# Homework2.net
KiCad netlist of a schematic drawn in EAGLE
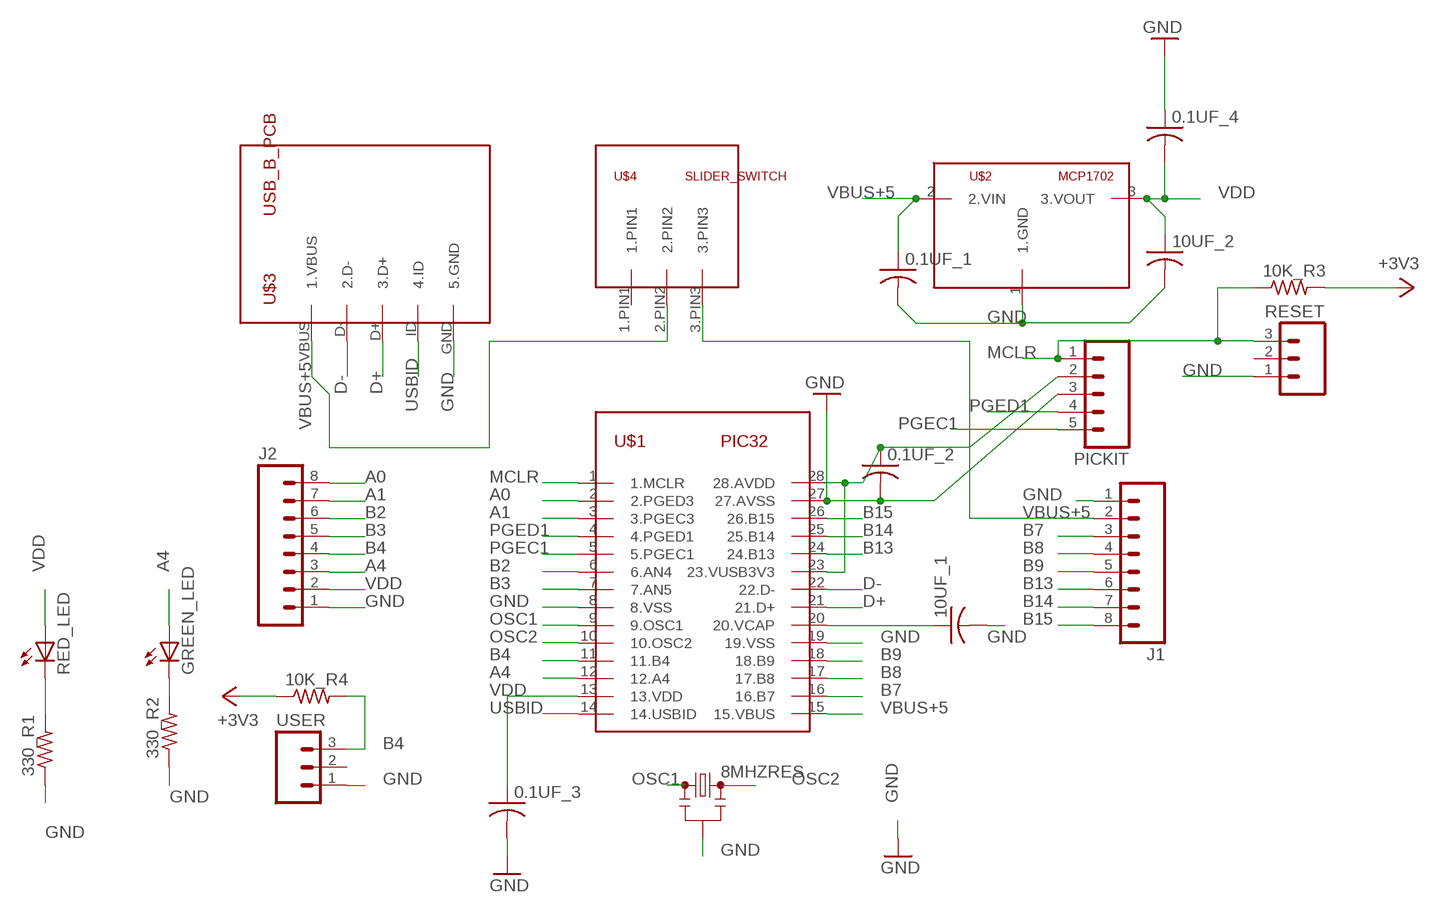
[diagram p0: schematic, sheet 1]

(export (version "E")
  (design (tool "Eeschema 10.0.6"))
  (components
    (comp (ref "0.1UF_1")
      (value "C-US025-024X044")
      (footprint "eagle-import:C025-024X044")
      (libsource (lib "eagle-import") (part "C-US025-024X044"))
    )
    (comp (ref "0.1UF_2")
      (value "C-US025-024X044")
      (footprint "eagle-import:C025-024X044")
      (libsource (lib "eagle-import") (part "C-US025-024X044"))
    )
    (comp (ref "0.1UF_3")
      (value "C-US025-024X044")
      (footprint "eagle-import:C025-024X044")
      (libsource (lib "eagle-import") (part "C-US025-024X044"))
    )
    (comp (ref "0.1UF_4")
      (value "C-US025-024X044")
      (footprint "eagle-import:C025-024X044")
      (libsource (lib "eagle-import") (part "C-US025-024X044"))
    )
    (comp (ref "8MHZRES")
      (value "RESONATORPTH")
      (footprint "eagle-import:RESONATOR-PTH")
      (libsource (lib "eagle-import") (part "RESONATORPTH"))
    )
    (comp (ref "10K_R3")
      (value "R-US_0204/5")
      (footprint "eagle-import:0204_5")
      (libsource (lib "eagle-import") (part "R-US_0204/5"))
    )
    (comp (ref "10K_R4")
      (value "R-US_0204/5")
      (footprint "eagle-import:0204_5")
      (libsource (lib "eagle-import") (part "R-US_0204/5"))
    )
    (comp (ref "10UF_1")
      (value "C-US050-024X044")
      (footprint "eagle-import:C050-024X044")
      (libsource (lib "eagle-import") (part "C-US050-024X044"))
    )
    (comp (ref "10UF_2")
      (value "C-US050-024X044")
      (footprint "eagle-import:C050-024X044")
      (libsource (lib "eagle-import") (part "C-US050-024X044"))
    )
    (comp (ref "330_R1")
      (value "R-US_0204/5")
      (footprint "eagle-import:0204_5")
      (libsource (lib "eagle-import") (part "R-US_0204/5"))
    )
    (comp (ref "330_R2")
      (value "R-US_0204/5")
      (footprint "eagle-import:0204_5")
      (libsource (lib "eagle-import") (part "R-US_0204/5"))
    )
    (comp (ref "GREEN_LED")
      (value "LED3MM")
      (footprint "eagle-import:LED3MM")
      (libsource (lib "eagle-import") (part "LED3MM"))
    )
    (comp (ref "J1")
      (value "M08SILK_FEMALE_PTH")
      (footprint "eagle-import:1X08")
      (libsource (lib "eagle-import") (part "M08SILK_FEMALE_PTH"))
    )
    (comp (ref "J2")
      (value "M08SILK_FEMALE_PTH")
      (footprint "eagle-import:1X08")
      (libsource (lib "eagle-import") (part "M08SILK_FEMALE_PTH"))
    )
    (comp (ref "PICKIT")
      (value "M05PTH")
      (footprint "eagle-import:1X05")
      (libsource (lib "eagle-import") (part "M05PTH"))
    )
    (comp (ref "RED_LED")
      (value "LED3MM")
      (footprint "eagle-import:LED3MM")
      (libsource (lib "eagle-import") (part "LED3MM"))
    )
    (comp (ref "RESET")
      (value "M03PTH")
      (footprint "eagle-import:1X03")
      (libsource (lib "eagle-import") (part "M03PTH"))
    )
    (comp (ref "U$1")
      (value "PIC32")
      (footprint "eagle-import:DIL28-3")
      (libsource (lib "eagle-import") (part "PIC32"))
    )
    (comp (ref "U$2")
      (value "MCP1702")
      (footprint "eagle-import:TO92")
      (libsource (lib "eagle-import") (part "MCP1702"))
    )
    (comp (ref "U$3")
      (value "USB_B_PCB")
      (footprint "eagle-import:USB-MB-H")
      (libsource (lib "eagle-import") (part "USB_B_PCB"))
    )
    (comp (ref "U$4")
      (value "SLIDER_SWITCH")
      (footprint "eagle-import:SLIDER_FOOTPRINT")
      (libsource (lib "eagle-import") (part "SLIDER_SWITCH"))
    )
    (comp (ref "USER")
      (value "M03PTH")
      (footprint "eagle-import:1X03")
      (libsource (lib "eagle-import") (part "M03PTH"))
    )
  )
  (nets
    (net (code "1") (name "+3V3") (class "Default")
      (node (ref "10K_R3") (pin "2") (pinfunction "2_2") (pintype "passive"))
      (node (ref "10K_R4") (pin "1") (pinfunction "1_1") (pintype "passive"))
    )
    (net (code "2") (name "A0") (class "Default")
      (node (ref "J2") (pin "8") (pinfunction "8_8") (pintype "passive"))
      (node (ref "U$1") (pin "2") (pinfunction "2.PGED3_2") (pintype "bidirectional"))
    )
    (net (code "3") (name "A1") (class "Default")
      (node (ref "J2") (pin "7") (pinfunction "7_7") (pintype "passive"))
      (node (ref "U$1") (pin "3") (pinfunction "3.PGEC3_3") (pintype "bidirectional"))
    )
    (net (code "4") (name "A4") (class "Default")
      (node (ref "GREEN_LED") (pin "A") (pinfunction "A_A") (pintype "passive"))
      (node (ref "J2") (pin "3") (pinfunction "3_3") (pintype "passive"))
      (node (ref "U$1") (pin "12") (pinfunction "12.A4_12") (pintype "bidirectional"))
    )
    (net (code "5") (name "B2") (class "Default")
      (node (ref "J2") (pin "6") (pinfunction "6_6") (pintype "passive"))
      (node (ref "U$1") (pin "6") (pinfunction "6.AN4_6") (pintype "bidirectional"))
    )
    (net (code "6") (name "B3") (class "Default")
      (node (ref "J2") (pin "5") (pinfunction "5_5") (pintype "passive"))
      (node (ref "U$1") (pin "7") (pinfunction "7.AN5_7") (pintype "bidirectional"))
    )
    (net (code "7") (name "B4") (class "Default")
      (node (ref "10K_R4") (pin "2") (pinfunction "2_2") (pintype "passive"))
      (node (ref "J2") (pin "4") (pinfunction "4_4") (pintype "passive"))
      (node (ref "U$1") (pin "11") (pinfunction "11.B4_11") (pintype "bidirectional"))
      (node (ref "USER") (pin "3") (pinfunction "3_3") (pintype "passive"))
    )
    (net (code "8") (name "B7") (class "Default")
      (node (ref "J1") (pin "3") (pinfunction "3_3") (pintype "passive"))
      (node (ref "U$1") (pin "16") (pinfunction "16.B7_16") (pintype "bidirectional"))
    )
    (net (code "9") (name "B8") (class "Default")
      (node (ref "J1") (pin "4") (pinfunction "4_4") (pintype "passive"))
      (node (ref "U$1") (pin "17") (pinfunction "17.B8_17") (pintype "bidirectional"))
    )
    (net (code "10") (name "B9") (class "Default")
      (node (ref "J1") (pin "5") (pinfunction "5_5") (pintype "passive"))
      (node (ref "U$1") (pin "18") (pinfunction "18.B9_18") (pintype "bidirectional"))
    )
    (net (code "11") (name "B13") (class "Default")
      (node (ref "J1") (pin "6") (pinfunction "6_6") (pintype "passive"))
      (node (ref "U$1") (pin "24") (pinfunction "24.B13_24") (pintype "bidirectional"))
    )
    (net (code "12") (name "B14") (class "Default")
      (node (ref "J1") (pin "7") (pinfunction "7_7") (pintype "passive"))
      (node (ref "U$1") (pin "25") (pinfunction "25.B14_25") (pintype "bidirectional"))
    )
    (net (code "13") (name "B15") (class "Default")
      (node (ref "J1") (pin "8") (pinfunction "8_8") (pintype "passive"))
      (node (ref "U$1") (pin "26") (pinfunction "26.B15_26") (pintype "bidirectional"))
    )
    (net (code "14") (name "D+") (class "Default")
      (node (ref "U$1") (pin "21") (pinfunction "21.D+_21") (pintype "bidirectional"))
      (node (ref "U$3") (pin "D+") (pinfunction "3.D+_D+") (pintype "bidirectional"))
    )
    (net (code "15") (name "D-") (class "Default")
      (node (ref "U$1") (pin "22") (pinfunction "22.D-_22") (pintype "bidirectional"))
      (node (ref "U$3") (pin "D-") (pinfunction "2.D-_D-") (pintype "bidirectional"))
    )
    (net (code "16") (name "GND") (class "Default")
      (node (ref "0.1UF_1") (pin "2") (pinfunction "2_2") (pintype "passive"))
      (node (ref "0.1UF_2") (pin "2") (pinfunction "2_2") (pintype "passive"))
      (node (ref "0.1UF_3") (pin "2") (pinfunction "2_2") (pintype "passive"))
      (node (ref "0.1UF_4") (pin "1") (pinfunction "1_1") (pintype "passive"))
      (node (ref "10UF_1") (pin "2") (pinfunction "2_2") (pintype "passive"))
      (node (ref "10UF_2") (pin "2") (pinfunction "2_2") (pintype "passive"))
      (node (ref "330_R1") (pin "1") (pinfunction "1_1") (pintype "passive"))
      (node (ref "330_R2") (pin "1") (pinfunction "1_1") (pintype "passive"))
      (node (ref "8MHZRES") (pin "2") (pinfunction "2_2") (pintype "passive"))
      (node (ref "J1") (pin "1") (pinfunction "1_1") (pintype "passive"))
      (node (ref "J2") (pin "1") (pinfunction "1_1") (pintype "passive"))
      (node (ref "PICKIT") (pin "3") (pinfunction "3_3") (pintype "passive"))
      (node (ref "RESET") (pin "1") (pinfunction "1_1") (pintype "passive"))
      (node (ref "U$1") (pin "19") (pinfunction "19.VSS_19") (pintype "bidirectional"))
      (node (ref "U$1") (pin "27") (pinfunction "27.AVSS_27") (pintype "bidirectional"))
      (node (ref "U$1") (pin "8") (pinfunction "8.VSS_8") (pintype "bidirectional"))
      (node (ref "U$2") (pin "1") (pinfunction "1.GND_1") (pintype "bidirectional"))
      (node (ref "U$3") (pin "GND") (pinfunction "5.GND_GND") (pintype "bidirectional"))
      (node (ref "USER") (pin "1") (pinfunction "1_1") (pintype "passive"))
    )
    (net (code "17") (name "MCLR") (class "Default")
      (node (ref "10K_R3") (pin "1") (pinfunction "1_1") (pintype "passive"))
      (node (ref "PICKIT") (pin "1") (pinfunction "1_1") (pintype "passive"))
      (node (ref "RESET") (pin "3") (pinfunction "3_3") (pintype "passive"))
      (node (ref "U$1") (pin "1") (pinfunction "1.MCLR_1") (pintype "bidirectional"))
    )
    (net (code "18") (name "Net-(GREEN_LED-C)") (class "Default")
      (node (ref "330_R2") (pin "2") (pinfunction "2_2") (pintype "passive"))
      (node (ref "GREEN_LED") (pin "K") (pinfunction "C_K") (pintype "passive"))
    )
    (net (code "19") (name "Net-(RED_LED-C)") (class "Default")
      (node (ref "330_R1") (pin "2") (pinfunction "2_2") (pintype "passive"))
      (node (ref "RED_LED") (pin "K") (pinfunction "C_K") (pintype "passive"))
    )
    (net (code "20") (name "Net-(U$1-20.VCAP)") (class "Default")
      (node (ref "10UF_1") (pin "1") (pinfunction "1_1") (pintype "passive"))
      (node (ref "U$1") (pin "20") (pinfunction "20.VCAP_20") (pintype "bidirectional"))
    )
    (net (code "21") (name "Net-(U$1-23.VUSB3V3)") (class "Default")
      (node (ref "0.1UF_2") (pin "1") (pinfunction "1_1") (pintype "passive"))
      (node (ref "PICKIT") (pin "2") (pinfunction "2_2") (pintype "passive"))
      (node (ref "U$1") (pin "23") (pinfunction "23.VUSB3V3_23") (pintype "bidirectional"))
      (node (ref "U$1") (pin "28") (pinfunction "28.AVDD_28") (pintype "bidirectional"))
    )
    (net (code "22") (name "OSC1") (class "Default")
      (node (ref "8MHZRES") (pin "1") (pinfunction "1_1") (pintype "passive"))
      (node (ref "U$1") (pin "9") (pinfunction "9.OSC1_9") (pintype "bidirectional"))
    )
    (net (code "23") (name "OSC2") (class "Default")
      (node (ref "8MHZRES") (pin "3") (pinfunction "3_3") (pintype "passive"))
      (node (ref "U$1") (pin "10") (pinfunction "10.OSC2_10") (pintype "bidirectional"))
    )
    (net (code "24") (name "PGEC1") (class "Default")
      (node (ref "PICKIT") (pin "5") (pinfunction "5_5") (pintype "passive"))
      (node (ref "U$1") (pin "5") (pinfunction "5.PGEC1_5") (pintype "bidirectional"))
    )
    (net (code "25") (name "PGED1") (class "Default")
      (node (ref "PICKIT") (pin "4") (pinfunction "4_4") (pintype "passive"))
      (node (ref "U$1") (pin "4") (pinfunction "4.PGED1_4") (pintype "bidirectional"))
    )
    (net (code "26") (name "USBID") (class "Default")
      (node (ref "U$1") (pin "14") (pinfunction "14.USBID_14") (pintype "bidirectional"))
      (node (ref "U$3") (pin "ID") (pinfunction "4.ID_ID") (pintype "bidirectional"))
    )
    (net (code "27") (name "VBUS+5") (class "Default")
      (node (ref "0.1UF_1") (pin "1") (pinfunction "1_1") (pintype "passive"))
      (node (ref "J1") (pin "2") (pinfunction "2_2") (pintype "passive"))
      (node (ref "U$1") (pin "15") (pinfunction "15.VBUS_15") (pintype "bidirectional"))
      (node (ref "U$2") (pin "2") (pinfunction "2.VIN_2") (pintype "bidirectional"))
      (node (ref "U$3") (pin "VBUS") (pinfunction "1.VBUS_VBUS") (pintype "bidirectional"))
      (node (ref "U$4") (pin "2.PIN2") (pinfunction "2.PIN2_2.PIN2") (pintype "bidirectional"))
      (node (ref "U$4") (pin "3.PIN3") (pinfunction "3.PIN3_3.PIN3") (pintype "bidirectional"))
    )
    (net (code "28") (name "VDD") (class "Default")
      (node (ref "0.1UF_3") (pin "1") (pinfunction "1_1") (pintype "passive"))
      (node (ref "0.1UF_4") (pin "2") (pinfunction "2_2") (pintype "passive"))
      (node (ref "10UF_2") (pin "1") (pinfunction "1_1") (pintype "passive"))
      (node (ref "J2") (pin "2") (pinfunction "2_2") (pintype "passive"))
      (node (ref "RED_LED") (pin "A") (pinfunction "A_A") (pintype "passive"))
      (node (ref "U$1") (pin "13") (pinfunction "13.VDD_13") (pintype "bidirectional"))
      (node (ref "U$2") (pin "3") (pinfunction "3.VOUT_3") (pintype "bidirectional"))
    )
    (net (code "29") (name "unconnected-(RESET-Pad2)") (class "Default")
      (node (ref "RESET") (pin "2") (pinfunction "2_2") (pintype "passive"))
    )
    (net (code "30") (name "unconnected-(U$4-Pad1.PIN1)") (class "Default")
      (node (ref "U$4") (pin "1.PIN1") (pinfunction "1.PIN1_1.PIN1") (pintype "bidirectional"))
    )
    (net (code "31") (name "unconnected-(USER-Pad2)") (class "Default")
      (node (ref "USER") (pin "2") (pinfunction "2_2") (pintype "passive"))
    )
  )
)
